# greippi_neg_boost.net
KiCad netlist of a schematic drawn in EAGLE
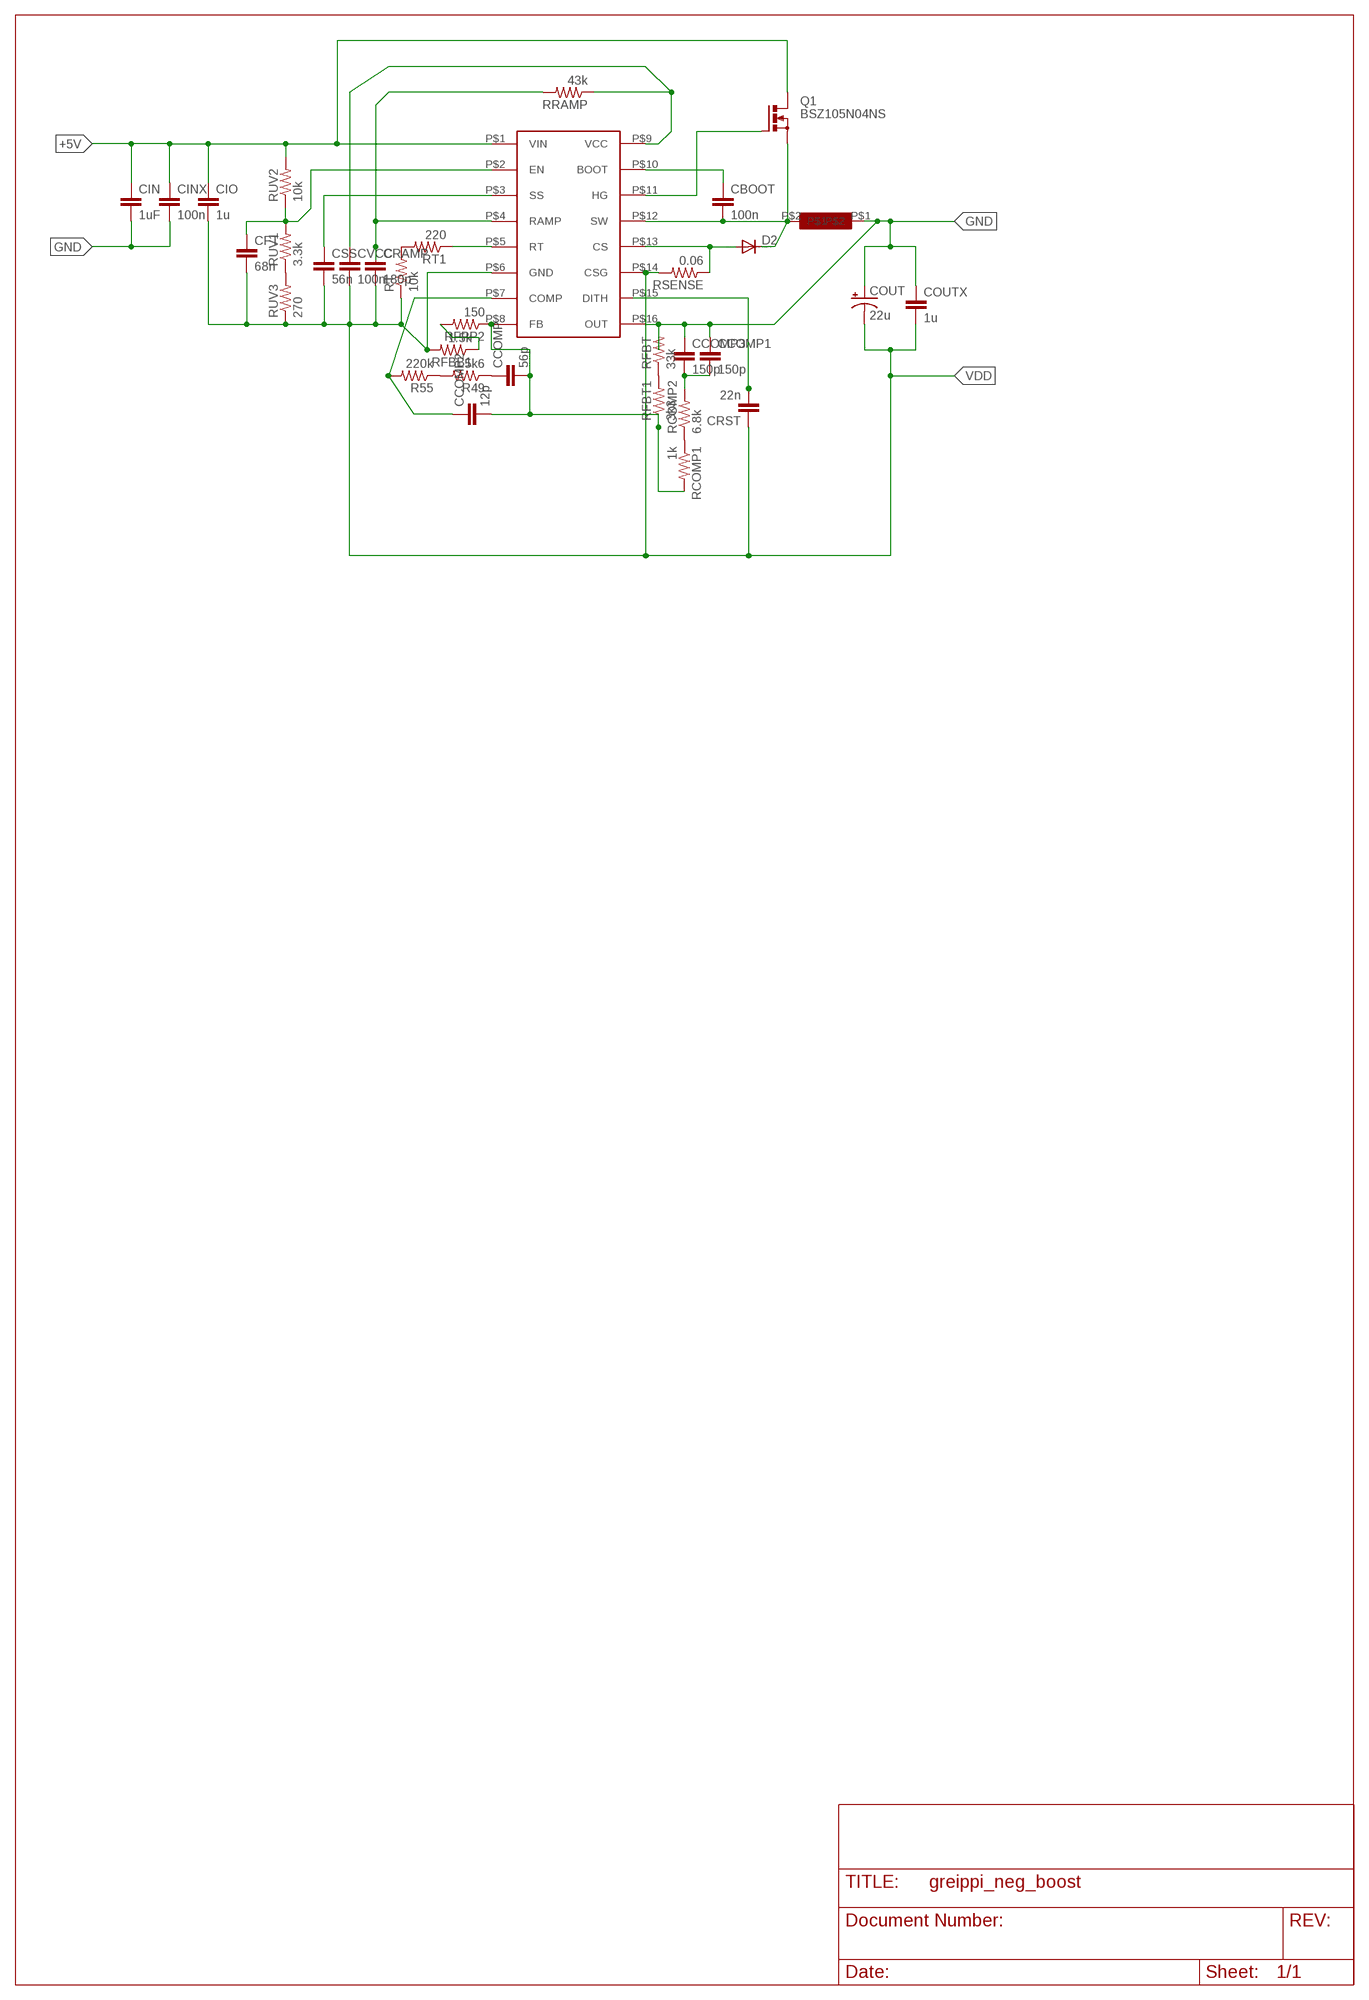
[diagram p0: schematic, sheet 1]

(export (version "E")
  (design (tool "Eeschema 10.0.6"))
  (components
    (comp (ref "CBOOT")
      (value "100n")
      (footprint "eagle-import:C0805")
      (libsource (lib "eagle-import") (part "C-EUC0805"))
    )
    (comp (ref "CCOMP")
      (value "56p")
      (footprint "eagle-import:C0805")
      (libsource (lib "eagle-import") (part "C-EUC0805"))
    )
    (comp (ref "CCOMP1")
      (value "150p")
      (footprint "eagle-import:C0805")
      (libsource (lib "eagle-import") (part "C-EUC0805"))
    )
    (comp (ref "CCOMP2")
      (value "12p")
      (footprint "eagle-import:C0805")
      (libsource (lib "eagle-import") (part "C-EUC0805"))
    )
    (comp (ref "CCOMP3")
      (value "150p")
      (footprint "eagle-import:C0805")
      (libsource (lib "eagle-import") (part "C-EUC0805"))
    )
    (comp (ref "CFT")
      (value "68n")
      (footprint "eagle-import:C0805")
      (libsource (lib "eagle-import") (part "C-EUC0805"))
    )
    (comp (ref "CIN")
      (value "1uF")
      (footprint "eagle-import:C0805")
      (libsource (lib "eagle-import") (part "C-EUC0805"))
    )
    (comp (ref "CINX")
      (value "100n")
      (footprint "eagle-import:C0805")
      (libsource (lib "eagle-import") (part "C-EUC0805"))
    )
    (comp (ref "CIO")
      (value "1u")
      (footprint "eagle-import:C0805")
      (libsource (lib "eagle-import") (part "C-EUC0805"))
    )
    (comp (ref "COUT")
      (value "22u")
      (footprint "eagle-import:E5-5")
      (libsource (lib "eagle-import") (part "CPOL-USE5-5"))
    )
    (comp (ref "COUTX")
      (value "1u")
      (footprint "eagle-import:C0805")
      (libsource (lib "eagle-import") (part "C-EUC0805"))
    )
    (comp (ref "CRAMP")
      (value "180p")
      (footprint "eagle-import:C0805")
      (libsource (lib "eagle-import") (part "C-EUC0805"))
    )
    (comp (ref "CRST")
      (value "22n")
      (footprint "eagle-import:C0805")
      (libsource (lib "eagle-import") (part "C-EUC0805"))
    )
    (comp (ref "CSS")
      (value "56n")
      (footprint "eagle-import:C0805")
      (libsource (lib "eagle-import") (part "C-EUC0805"))
    )
    (comp (ref "CVCC")
      (value "100n")
      (footprint "eagle-import:C0805")
      (libsource (lib "eagle-import") (part "C-EUC0805"))
    )
    (comp (ref "D2")
      (value "DIODE-SOD123")
      (footprint "eagle-import:SOD123")
      (libsource (lib "eagle-import") (part "DIODE-SOD123"))
    )
    (comp (ref "Q1")
      (value "BSZ105N04NS")
      (footprint "eagle-import:PG-TDSON-8")
      (libsource (lib "eagle-import") (part "BSZ105N04NS"))
    )
    (comp (ref "R49")
      (value "5k6")
      (footprint "eagle-import:R0805")
      (libsource (lib "eagle-import") (part "R-US_R0805"))
    )
    (comp (ref "R55")
      (value "220k")
      (footprint "eagle-import:R0805")
      (libsource (lib "eagle-import") (part "R-US_R0805"))
    )
    (comp (ref "RCOMP1")
      (value "1k")
      (footprint "eagle-import:R0805")
      (libsource (lib "eagle-import") (part "R-US_R0805"))
    )
    (comp (ref "RCOMP2")
      (value "6.8k")
      (footprint "eagle-import:R0805")
      (libsource (lib "eagle-import") (part "R-US_R0805"))
    )
    (comp (ref "RFBB1")
      (value "1.5k")
      (footprint "eagle-import:R0805")
      (libsource (lib "eagle-import") (part "R-US_R0805"))
    )
    (comp (ref "RFBT")
      (value "33k")
      (footprint "eagle-import:R0805")
      (libsource (lib "eagle-import") (part "R-US_R0805"))
    )
    (comp (ref "RFBT1")
      (value "3k3")
      (footprint "eagle-import:R0805")
      (libsource (lib "eagle-import") (part "R-US_R0805"))
    )
    (comp (ref "RFPP2")
      (value "150")
      (footprint "eagle-import:R0805")
      (libsource (lib "eagle-import") (part "R-US_R0805"))
    )
    (comp (ref "RRAMP")
      (value "43k")
      (footprint "eagle-import:R0805")
      (libsource (lib "eagle-import") (part "R-US_R0805"))
    )
    (comp (ref "RSENSE")
      (value "0.06")
      (footprint "eagle-import:R0805")
      (libsource (lib "eagle-import") (part "R-US_R0805"))
    )
    (comp (ref "RT")
      (value "10k")
      (footprint "eagle-import:R0805")
      (libsource (lib "eagle-import") (part "R-US_R0805"))
    )
    (comp (ref "RT1")
      (value "220")
      (footprint "eagle-import:R0805")
      (libsource (lib "eagle-import") (part "R-US_R0805"))
    )
    (comp (ref "RUV1")
      (value "3.3k")
      (footprint "eagle-import:R0805")
      (libsource (lib "eagle-import") (part "R-US_R0805"))
    )
    (comp (ref "RUV2")
      (value "10k")
      (footprint "eagle-import:R0805")
      (libsource (lib "eagle-import") (part "R-US_R0805"))
    )
    (comp (ref "RUV3")
      (value "270")
      (footprint "eagle-import:R0805")
      (libsource (lib "eagle-import") (part "R-US_R0805"))
    )
    (comp (ref "U$2")
      (value "LM5088")
      (footprint "eagle-import:LM5088")
      (libsource (lib "eagle-import") (part "LM5088"))
    )
    (comp (ref "U$3")
      (value "KLICK_INDUCTOR01")
      (footprint "eagle-import:KLICK_INDUCTOR01")
      (libsource (lib "eagle-import") (part "KLICK_INDUCTOR01"))
    )
  )
  (nets
    (net (code "1") (name "+5V") (class "Default")
      (node (ref "CIN") (pin "1") (pinfunction "1_1") (pintype "passive"))
      (node (ref "CINX") (pin "1") (pinfunction "1_1") (pintype "passive"))
      (node (ref "CIO") (pin "1") (pinfunction "1_1") (pintype "passive"))
      (node (ref "Q1") (pin "5") (pinfunction "D_5") (pintype "passive"))
      (node (ref "Q1") (pin "6") (pinfunction "D_6") (pintype "passive"))
      (node (ref "Q1") (pin "7") (pinfunction "D_7") (pintype "passive"))
      (node (ref "Q1") (pin "8") (pinfunction "D_8") (pintype "passive"))
      (node (ref "Q1") (pin "TH") (pinfunction "D_TH") (pintype "passive"))
      (node (ref "RUV2") (pin "2") (pinfunction "2_2") (pintype "passive"))
      (node (ref "U$2") (pin "P$1") (pinfunction "VIN_P$1") (pintype "bidirectional"))
    )
    (net (code "2") (name "GND") (class "Default")
      (node (ref "CCOMP1") (pin "1") (pinfunction "1_1") (pintype "passive"))
      (node (ref "CCOMP3") (pin "1") (pinfunction "1_1") (pintype "passive"))
      (node (ref "CIN") (pin "2") (pinfunction "2_2") (pintype "passive"))
      (node (ref "CINX") (pin "2") (pinfunction "2_2") (pintype "passive"))
      (node (ref "COUT") (pin "+") (pinfunction "+_+") (pintype "passive"))
      (node (ref "COUTX") (pin "1") (pinfunction "1_1") (pintype "passive"))
      (node (ref "RFBT") (pin "2") (pinfunction "2_2") (pintype "passive"))
      (node (ref "U$2") (pin "P$16") (pinfunction "OUT_P$16") (pintype "bidirectional"))
      (node (ref "U$3") (pin "P$1") (pinfunction "P$1_P$1") (pintype "bidirectional"))
    )
    (net (code "3") (name "Net-(CCOMP-Pad1)") (class "Default")
      (node (ref "CCOMP") (pin "1") (pinfunction "1_1") (pintype "passive"))
      (node (ref "R49") (pin "1") (pinfunction "1_1") (pintype "passive"))
    )
    (net (code "4") (name "Net-(CCOMP1-Pad2)") (class "Default")
      (node (ref "CCOMP1") (pin "2") (pinfunction "2_2") (pintype "passive"))
      (node (ref "CCOMP3") (pin "2") (pinfunction "2_2") (pintype "passive"))
      (node (ref "RCOMP2") (pin "2") (pinfunction "2_2") (pintype "passive"))
    )
    (net (code "5") (name "Net-(Q1-G)") (class "Default")
      (node (ref "Q1") (pin "4") (pinfunction "G_4") (pintype "passive"))
      (node (ref "U$2") (pin "P$11") (pinfunction "HG_P$11") (pintype "bidirectional"))
    )
    (net (code "6") (name "Net-(R49-Pad2)") (class "Default")
      (node (ref "R49") (pin "2") (pinfunction "2_2") (pintype "passive"))
      (node (ref "R55") (pin "1") (pinfunction "1_1") (pintype "passive"))
    )
    (net (code "7") (name "Net-(RCOMP1-Pad1)") (class "Default")
      (node (ref "RCOMP1") (pin "1") (pinfunction "1_1") (pintype "passive"))
      (node (ref "RCOMP2") (pin "1") (pinfunction "1_1") (pintype "passive"))
    )
    (net (code "8") (name "Net-(RFBB1-Pad1)") (class "Default")
      (node (ref "RFBB1") (pin "1") (pinfunction "1_1") (pintype "passive"))
      (node (ref "RFPP2") (pin "2") (pinfunction "2_2") (pintype "passive"))
    )
    (net (code "9") (name "Net-(RFBT-Pad1)") (class "Default")
      (node (ref "RFBT") (pin "1") (pinfunction "1_1") (pintype "passive"))
      (node (ref "RFBT1") (pin "2") (pinfunction "2_2") (pintype "passive"))
    )
    (net (code "10") (name "Net-(RT-Pad2)") (class "Default")
      (node (ref "RT") (pin "2") (pinfunction "2_2") (pintype "passive"))
      (node (ref "RT1") (pin "2") (pinfunction "2_2") (pintype "passive"))
    )
    (net (code "11") (name "Net-(RUV1-Pad1)") (class "Default")
      (node (ref "RUV1") (pin "1") (pinfunction "1_1") (pintype "passive"))
      (node (ref "RUV3") (pin "2") (pinfunction "2_2") (pintype "passive"))
    )
    (net (code "12") (name "Net-(U$2-BOOT)") (class "Default")
      (node (ref "CBOOT") (pin "1") (pinfunction "1_1") (pintype "passive"))
      (node (ref "U$2") (pin "P$10") (pinfunction "BOOT_P$10") (pintype "bidirectional"))
    )
    (net (code "13") (name "Net-(U$2-COMP)") (class "Default")
      (node (ref "CCOMP2") (pin "1") (pinfunction "1_1") (pintype "passive"))
      (node (ref "R55") (pin "2") (pinfunction "2_2") (pintype "passive"))
      (node (ref "U$2") (pin "P$7") (pinfunction "COMP_P$7") (pintype "bidirectional"))
    )
    (net (code "14") (name "Net-(U$2-CS)") (class "Default")
      (node (ref "D2") (pin "A") (pinfunction "A_A") (pintype "passive"))
      (node (ref "RSENSE") (pin "1") (pinfunction "1_1") (pintype "passive"))
      (node (ref "U$2") (pin "P$13") (pinfunction "CS_P$13") (pintype "bidirectional"))
    )
    (net (code "15") (name "Net-(U$2-DITH)") (class "Default")
      (node (ref "CRST") (pin "2") (pinfunction "2_2") (pintype "passive"))
      (node (ref "U$2") (pin "P$15") (pinfunction "DITH_P$15") (pintype "bidirectional"))
    )
    (net (code "16") (name "Net-(U$2-EN)") (class "Default")
      (node (ref "CFT") (pin "1") (pinfunction "1_1") (pintype "passive"))
      (node (ref "RUV1") (pin "2") (pinfunction "2_2") (pintype "passive"))
      (node (ref "RUV2") (pin "1") (pinfunction "1_1") (pintype "passive"))
      (node (ref "U$2") (pin "P$2") (pinfunction "EN_P$2") (pintype "bidirectional"))
    )
    (net (code "17") (name "Net-(U$2-FB)") (class "Default")
      (node (ref "CCOMP") (pin "2") (pinfunction "2_2") (pintype "passive"))
      (node (ref "CCOMP2") (pin "2") (pinfunction "2_2") (pintype "passive"))
      (node (ref "RCOMP1") (pin "2") (pinfunction "2_2") (pintype "passive"))
      (node (ref "RFBT1") (pin "1") (pinfunction "1_1") (pintype "passive"))
      (node (ref "RFPP2") (pin "1") (pinfunction "1_1") (pintype "passive"))
      (node (ref "U$2") (pin "P$8") (pinfunction "FB_P$8") (pintype "bidirectional"))
    )
    (net (code "18") (name "Net-(U$2-RAMP)") (class "Default")
      (node (ref "CRAMP") (pin "1") (pinfunction "1_1") (pintype "passive"))
      (node (ref "RRAMP") (pin "2") (pinfunction "2_2") (pintype "passive"))
      (node (ref "U$2") (pin "P$4") (pinfunction "RAMP_P$4") (pintype "bidirectional"))
    )
    (net (code "19") (name "Net-(U$2-RT)") (class "Default")
      (node (ref "RT1") (pin "1") (pinfunction "1_1") (pintype "passive"))
      (node (ref "U$2") (pin "P$5") (pinfunction "RT_P$5") (pintype "bidirectional"))
    )
    (net (code "20") (name "Net-(U$2-SS)") (class "Default")
      (node (ref "CSS") (pin "1") (pinfunction "1_1") (pintype "passive"))
      (node (ref "U$2") (pin "P$3") (pinfunction "SS_P$3") (pintype "bidirectional"))
    )
    (net (code "21") (name "Net-(U$2-SW)") (class "Default")
      (node (ref "CBOOT") (pin "2") (pinfunction "2_2") (pintype "passive"))
      (node (ref "D2") (pin "C") (pinfunction "C_C") (pintype "passive"))
      (node (ref "Q1") (pin "1") (pinfunction "S_1") (pintype "passive"))
      (node (ref "Q1") (pin "2") (pinfunction "S_2") (pintype "passive"))
      (node (ref "Q1") (pin "3") (pinfunction "S_3") (pintype "passive"))
      (node (ref "U$2") (pin "P$12") (pinfunction "SW_P$12") (pintype "bidirectional"))
      (node (ref "U$3") (pin "P$2") (pinfunction "P$2_P$2") (pintype "bidirectional"))
    )
    (net (code "22") (name "Net-(U$2-VCC)") (class "Default")
      (node (ref "CVCC") (pin "1") (pinfunction "1_1") (pintype "passive"))
      (node (ref "RRAMP") (pin "1") (pinfunction "1_1") (pintype "passive"))
      (node (ref "U$2") (pin "P$9") (pinfunction "VCC_P$9") (pintype "bidirectional"))
    )
    (net (code "23") (name "VDD") (class "Default")
      (node (ref "CFT") (pin "2") (pinfunction "2_2") (pintype "passive"))
      (node (ref "CIO") (pin "2") (pinfunction "2_2") (pintype "passive"))
      (node (ref "COUT") (pin "-") (pinfunction "-_-") (pintype "passive"))
      (node (ref "COUTX") (pin "2") (pinfunction "2_2") (pintype "passive"))
      (node (ref "CRAMP") (pin "2") (pinfunction "2_2") (pintype "passive"))
      (node (ref "CRST") (pin "1") (pinfunction "1_1") (pintype "passive"))
      (node (ref "CSS") (pin "2") (pinfunction "2_2") (pintype "passive"))
      (node (ref "CVCC") (pin "2") (pinfunction "2_2") (pintype "passive"))
      (node (ref "RFBB1") (pin "2") (pinfunction "2_2") (pintype "passive"))
      (node (ref "RSENSE") (pin "2") (pinfunction "2_2") (pintype "passive"))
      (node (ref "RT") (pin "1") (pinfunction "1_1") (pintype "passive"))
      (node (ref "RUV3") (pin "1") (pinfunction "1_1") (pintype "passive"))
      (node (ref "U$2") (pin "P$14") (pinfunction "CSG_P$14") (pintype "bidirectional"))
      (node (ref "U$2") (pin "P$6") (pinfunction "GND_P$6") (pintype "bidirectional"))
    )
  )
)
